# SlaveDual.net
KiCad netlist of a schematic drawn in EAGLE
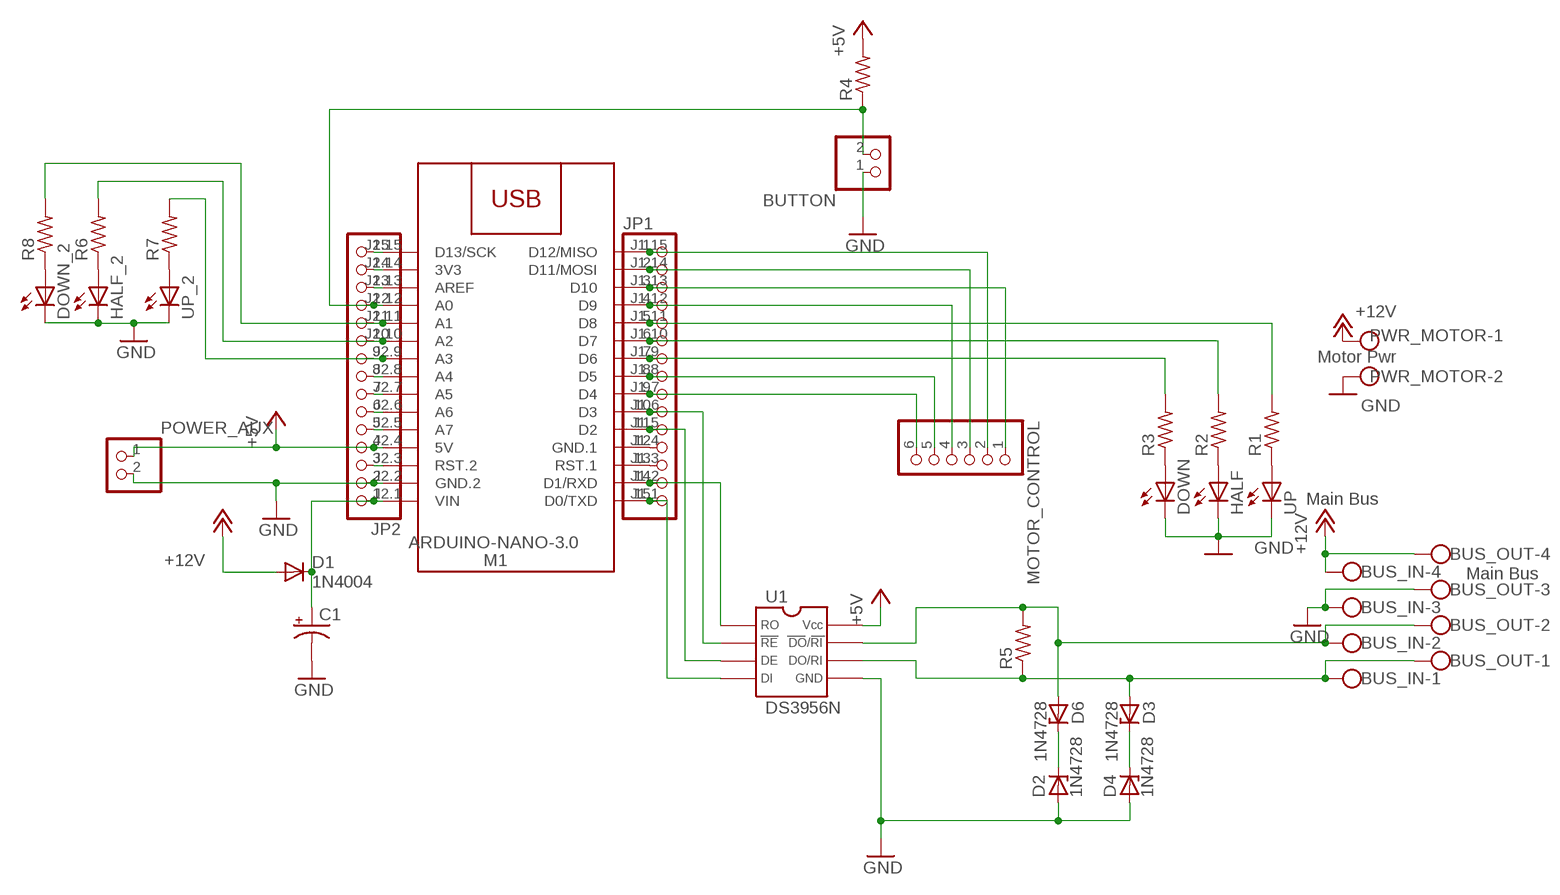
[diagram p0: schematic, sheet 1]

(export (version "E")
  (design (tool "Eeschema 10.0.6"))
  (components
    (comp (ref "BUS_IN")
      (value "Main Bus")
      (footprint "eagle-import:W237-4")
      (libsource (lib "eagle-import") (part "W237-4"))
    )
    (comp (ref "BUS_OUT")
      (value "Main Bus")
      (footprint "eagle-import:W237-4")
      (libsource (lib "eagle-import") (part "W237-4"))
    )
    (comp (ref "BUTTON")
      (value "PINHD-1X2")
      (footprint "eagle-import:1X02")
      (libsource (lib "eagle-import") (part "PINHD-1X2"))
    )
    (comp (ref "C1")
      (value "CPOL-USE3.5-10")
      (footprint "eagle-import:E3,5-10")
      (libsource (lib "eagle-import") (part "CPOL-USE3.5-10"))
    )
    (comp (ref "D1")
      (value "1N4004")
      (footprint "eagle-import:DO41-10")
      (libsource (lib "eagle-import") (part "1N4004"))
    )
    (comp (ref "D2")
      (value "1N4728")
      (footprint "eagle-import:DO41Z10")
      (libsource (lib "eagle-import") (part "1N4728"))
    )
    (comp (ref "D3")
      (value "1N4728")
      (footprint "eagle-import:DO41Z10")
      (libsource (lib "eagle-import") (part "1N4728"))
    )
    (comp (ref "D4")
      (value "1N4728")
      (footprint "eagle-import:DO41Z10")
      (libsource (lib "eagle-import") (part "1N4728"))
    )
    (comp (ref "D6")
      (value "1N4728")
      (footprint "eagle-import:DO41Z10")
      (libsource (lib "eagle-import") (part "1N4728"))
    )
    (comp (ref "DOWN")
      (value "LED5MM")
      (footprint "eagle-import:LED5MM")
      (libsource (lib "eagle-import") (part "LED5MM"))
    )
    (comp (ref "DOWN_2")
      (value "LED5MM")
      (footprint "eagle-import:LED5MM")
      (libsource (lib "eagle-import") (part "LED5MM"))
    )
    (comp (ref "HALF")
      (value "LED5MM")
      (footprint "eagle-import:LED5MM")
      (libsource (lib "eagle-import") (part "LED5MM"))
    )
    (comp (ref "HALF_2")
      (value "LED5MM")
      (footprint "eagle-import:LED5MM")
      (libsource (lib "eagle-import") (part "LED5MM"))
    )
    (comp (ref "JP1")
      (value "PINHD-1X15-CB")
      (footprint "eagle-import:1X15-CB")
      (libsource (lib "eagle-import") (part "PINHD-1X15-CB"))
    )
    (comp (ref "JP2")
      (value "PINHD-1X15-CB")
      (footprint "eagle-import:1X15-CB")
      (libsource (lib "eagle-import") (part "PINHD-1X15-CB"))
    )
    (comp (ref "M1")
      (value "ARDUINO-NANO-3.0")
      (footprint "eagle-import:ARDUINO-NANO-3.0")
      (libsource (lib "eagle-import") (part "ARDUINO-NANO-3.0"))
    )
    (comp (ref "MOTOR_CONTROL")
      (value "PINHD-1X6")
      (footprint "eagle-import:1X06")
      (libsource (lib "eagle-import") (part "PINHD-1X6"))
    )
    (comp (ref "POWER_AUX")
      (value "PINHD-1X2")
      (footprint "eagle-import:1X02")
      (libsource (lib "eagle-import") (part "PINHD-1X2"))
    )
    (comp (ref "PWR_MOTOR")
      (value "Motor Pwr")
      (footprint "eagle-import:W237-102")
      (fields (field (name "MPN") "237-102"))
      (libsource (lib "eagle-import") (part "W237-102"))
    )
    (comp (ref "R1")
      (value "FLIPFLOP-RES")
      (footprint "eagle-import:0805-THM")
      (libsource (lib "eagle-import") (part "FLIPFLOP-RES"))
    )
    (comp (ref "R2")
      (value "FLIPFLOP-RES")
      (footprint "eagle-import:0805-THM")
      (libsource (lib "eagle-import") (part "FLIPFLOP-RES"))
    )
    (comp (ref "R3")
      (value "FLIPFLOP-RES")
      (footprint "eagle-import:0805-THM")
      (libsource (lib "eagle-import") (part "FLIPFLOP-RES"))
    )
    (comp (ref "R4")
      (value "FLIPFLOP-RES")
      (footprint "eagle-import:0805-THM")
      (libsource (lib "eagle-import") (part "FLIPFLOP-RES"))
    )
    (comp (ref "R5")
      (value "FLIPFLOP-RES")
      (footprint "eagle-import:0805-THM")
      (libsource (lib "eagle-import") (part "FLIPFLOP-RES"))
    )
    (comp (ref "R6")
      (value "FLIPFLOP-RES")
      (footprint "eagle-import:0805-THM")
      (libsource (lib "eagle-import") (part "FLIPFLOP-RES"))
    )
    (comp (ref "R7")
      (value "FLIPFLOP-RES")
      (footprint "eagle-import:0805-THM")
      (libsource (lib "eagle-import") (part "FLIPFLOP-RES"))
    )
    (comp (ref "R8")
      (value "FLIPFLOP-RES")
      (footprint "eagle-import:0805-THM")
      (libsource (lib "eagle-import") (part "FLIPFLOP-RES"))
    )
    (comp (ref "U1")
      (value "DS3956N")
      (footprint "eagle-import:DIL08")
      (libsource (lib "eagle-import") (part "DS3956N"))
    )
    (comp (ref "UP")
      (value "LED5MM")
      (footprint "eagle-import:LED5MM")
      (libsource (lib "eagle-import") (part "LED5MM"))
    )
    (comp (ref "UP_2")
      (value "LED5MM")
      (footprint "eagle-import:LED5MM")
      (libsource (lib "eagle-import") (part "LED5MM"))
    )
  )
  (nets
    (net (code "1") (name "+5V") (class "Default")
      (node (ref "JP2") (pin "4") (pinfunction "4_4") (pintype "passive"))
      (node (ref "M1") (pin "J2.4") (pinfunction "5V_J2.4") (pintype "power_in"))
      (node (ref "POWER_AUX") (pin "1") (pinfunction "1_1") (pintype "passive"))
      (node (ref "R4") (pin "2") (pinfunction "2_2") (pintype "passive"))
      (node (ref "U1") (pin "8") (pinfunction "VCC_8") (pintype "bidirectional"))
    )
    (net (code "2") (name "+12V") (class "Default")
      (node (ref "BUS_IN") (pin "4") (pinfunction "KL_4") (pintype "passive"))
      (node (ref "BUS_OUT") (pin "4") (pinfunction "KL_4") (pintype "passive"))
      (node (ref "D1") (pin "A") (pinfunction "A_A") (pintype "passive"))
      (node (ref "PWR_MOTOR") (pin "1") (pinfunction "KL_1") (pintype "passive"))
    )
    (net (code "3") (name "GND") (class "Default")
      (node (ref "BUS_IN") (pin "3") (pinfunction "KL_3") (pintype "passive"))
      (node (ref "BUS_OUT") (pin "3") (pinfunction "KL_3") (pintype "passive"))
      (node (ref "BUTTON") (pin "1") (pinfunction "1_1") (pintype "passive"))
      (node (ref "C1") (pin "-") (pinfunction "-_-") (pintype "passive"))
      (node (ref "D2") (pin "A") (pinfunction "A_A") (pintype "passive"))
      (node (ref "D4") (pin "A") (pinfunction "A_A") (pintype "passive"))
      (node (ref "DOWN") (pin "K") (pinfunction "C_K") (pintype "passive"))
      (node (ref "DOWN_2") (pin "K") (pinfunction "C_K") (pintype "passive"))
      (node (ref "HALF") (pin "K") (pinfunction "C_K") (pintype "passive"))
      (node (ref "HALF_2") (pin "K") (pinfunction "C_K") (pintype "passive"))
      (node (ref "JP2") (pin "2") (pinfunction "2_2") (pintype "passive"))
      (node (ref "M1") (pin "J2.2") (pinfunction "GND.2_J2.2") (pintype "power_in"))
      (node (ref "POWER_AUX") (pin "2") (pinfunction "2_2") (pintype "passive"))
      (node (ref "PWR_MOTOR") (pin "2") (pinfunction "KL_2") (pintype "passive"))
      (node (ref "U1") (pin "5") (pinfunction "GND_5") (pintype "bidirectional"))
      (node (ref "UP") (pin "K") (pinfunction "C_K") (pintype "passive"))
      (node (ref "UP_2") (pin "K") (pinfunction "C_K") (pintype "passive"))
    )
    (net (code "4") (name "Net-(BUS_INA-KL)") (class "Default")
      (node (ref "BUS_IN") (pin "1") (pinfunction "KL_1") (pintype "passive"))
      (node (ref "BUS_OUT") (pin "1") (pinfunction "KL_1") (pintype "passive"))
      (node (ref "D3") (pin "A") (pinfunction "A_A") (pintype "passive"))
      (node (ref "R5") (pin "1") (pinfunction "1_1") (pintype "passive"))
      (node (ref "U1") (pin "6") (pinfunction "DO/RI_6") (pintype "bidirectional"))
    )
    (net (code "5") (name "Net-(BUS_INB-KL)") (class "Default")
      (node (ref "BUS_IN") (pin "2") (pinfunction "KL_2") (pintype "passive"))
      (node (ref "BUS_OUT") (pin "2") (pinfunction "KL_2") (pintype "passive"))
      (node (ref "D6") (pin "A") (pinfunction "A_A") (pintype "passive"))
      (node (ref "R5") (pin "2") (pinfunction "2_2") (pintype "passive"))
      (node (ref "U1") (pin "7") (pinfunction "_DO/RI__7") (pintype "bidirectional"))
    )
    (net (code "6") (name "Net-(D2-PadC)") (class "Default")
      (node (ref "D2") (pin "C") (pinfunction "C_C") (pintype "passive"))
      (node (ref "D6") (pin "C") (pinfunction "C_C") (pintype "passive"))
    )
    (net (code "7") (name "Net-(D3-PadC)") (class "Default")
      (node (ref "D3") (pin "C") (pinfunction "C_C") (pintype "passive"))
      (node (ref "D4") (pin "C") (pinfunction "C_C") (pintype "passive"))
    )
    (net (code "8") (name "Net-(DOWN-PadA)") (class "Default")
      (node (ref "DOWN") (pin "A") (pinfunction "A_A") (pintype "passive"))
      (node (ref "R3") (pin "1") (pinfunction "1_1") (pintype "passive"))
    )
    (net (code "9") (name "Net-(DOWN_2-PadA)") (class "Default")
      (node (ref "DOWN_2") (pin "A") (pinfunction "A_A") (pintype "passive"))
      (node (ref "R8") (pin "1") (pinfunction "1_1") (pintype "passive"))
    )
    (net (code "10") (name "Net-(HALF-PadA)") (class "Default")
      (node (ref "HALF") (pin "A") (pinfunction "A_A") (pintype "passive"))
      (node (ref "R2") (pin "1") (pinfunction "1_1") (pintype "passive"))
    )
    (net (code "11") (name "Net-(HALF_2-PadA)") (class "Default")
      (node (ref "HALF_2") (pin "A") (pinfunction "A_A") (pintype "passive"))
      (node (ref "R6") (pin "1") (pinfunction "1_1") (pintype "passive"))
    )
    (net (code "12") (name "Net-(M1-3V3)") (class "Default")
      (node (ref "JP2") (pin "14") (pinfunction "14_14") (pintype "passive"))
      (node (ref "M1") (pin "J2.14") (pinfunction "3V3_J2.14") (pintype "power_in"))
    )
    (net (code "13") (name "Net-(M1-A0)") (class "Default")
      (node (ref "BUTTON") (pin "2") (pinfunction "2_2") (pintype "passive"))
      (node (ref "JP2") (pin "12") (pinfunction "12_12") (pintype "passive"))
      (node (ref "M1") (pin "J2.12") (pinfunction "A0_J2.12") (pintype "bidirectional"))
      (node (ref "R4") (pin "1") (pinfunction "1_1") (pintype "passive"))
    )
    (net (code "14") (name "Net-(M1-A1)") (class "Default")
      (node (ref "JP2") (pin "11") (pinfunction "11_11") (pintype "passive"))
      (node (ref "M1") (pin "J2.11") (pinfunction "A1_J2.11") (pintype "bidirectional"))
      (node (ref "R8") (pin "2") (pinfunction "2_2") (pintype "passive"))
    )
    (net (code "15") (name "Net-(M1-A2)") (class "Default")
      (node (ref "JP2") (pin "10") (pinfunction "10_10") (pintype "passive"))
      (node (ref "M1") (pin "J2.10") (pinfunction "A2_J2.10") (pintype "bidirectional"))
      (node (ref "R6") (pin "2") (pinfunction "2_2") (pintype "passive"))
    )
    (net (code "16") (name "Net-(M1-A3)") (class "Default")
      (node (ref "JP2") (pin "9") (pinfunction "9_9") (pintype "passive"))
      (node (ref "M1") (pin "J2.9") (pinfunction "A3_J2.9") (pintype "bidirectional"))
      (node (ref "R7") (pin "2") (pinfunction "2_2") (pintype "passive"))
    )
    (net (code "17") (name "Net-(M1-A4)") (class "Default")
      (node (ref "JP2") (pin "8") (pinfunction "8_8") (pintype "passive"))
      (node (ref "M1") (pin "J2.8") (pinfunction "A4_J2.8") (pintype "bidirectional"))
    )
    (net (code "18") (name "Net-(M1-A5)") (class "Default")
      (node (ref "JP2") (pin "7") (pinfunction "7_7") (pintype "passive"))
      (node (ref "M1") (pin "J2.7") (pinfunction "A5_J2.7") (pintype "bidirectional"))
    )
    (net (code "19") (name "Net-(M1-A6)") (class "Default")
      (node (ref "JP2") (pin "6") (pinfunction "6_6") (pintype "passive"))
      (node (ref "M1") (pin "J2.6") (pinfunction "A6_J2.6") (pintype "bidirectional"))
    )
    (net (code "20") (name "Net-(M1-A7)") (class "Default")
      (node (ref "JP2") (pin "5") (pinfunction "5_5") (pintype "passive"))
      (node (ref "M1") (pin "J2.5") (pinfunction "A7_J2.5") (pintype "bidirectional"))
    )
    (net (code "21") (name "Net-(M1-AREF)") (class "Default")
      (node (ref "JP2") (pin "13") (pinfunction "13_13") (pintype "passive"))
      (node (ref "M1") (pin "J2.13") (pinfunction "AREF_J2.13") (pintype "bidirectional"))
    )
    (net (code "22") (name "Net-(M1-D0{slash}TXD)") (class "Default")
      (node (ref "JP1") (pin "15") (pinfunction "15_15") (pintype "passive"))
      (node (ref "M1") (pin "J1.1") (pinfunction "D0/TXD_J1.1") (pintype "bidirectional"))
      (node (ref "U1") (pin "4") (pinfunction "DI_4") (pintype "bidirectional"))
    )
    (net (code "23") (name "Net-(M1-D1{slash}RXD)") (class "Default")
      (node (ref "JP1") (pin "14") (pinfunction "14_14") (pintype "passive"))
      (node (ref "M1") (pin "J1.2") (pinfunction "D1/RXD_J1.2") (pintype "bidirectional"))
      (node (ref "U1") (pin "1") (pinfunction "RO_1") (pintype "bidirectional"))
    )
    (net (code "24") (name "Net-(M1-D2)") (class "Default")
      (node (ref "JP1") (pin "11") (pinfunction "11_11") (pintype "passive"))
      (node (ref "M1") (pin "J1.5") (pinfunction "D2_J1.5") (pintype "bidirectional"))
      (node (ref "U1") (pin "3") (pinfunction "DE_3") (pintype "bidirectional"))
    )
    (net (code "25") (name "Net-(M1-D3)") (class "Default")
      (node (ref "JP1") (pin "10") (pinfunction "10_10") (pintype "passive"))
      (node (ref "M1") (pin "J1.6") (pinfunction "D3_J1.6") (pintype "bidirectional"))
      (node (ref "U1") (pin "2") (pinfunction "_RE__2") (pintype "bidirectional"))
    )
    (net (code "26") (name "Net-(M1-D4)") (class "Default")
      (node (ref "JP1") (pin "9") (pinfunction "9_9") (pintype "passive"))
      (node (ref "M1") (pin "J1.7") (pinfunction "D4_J1.7") (pintype "bidirectional"))
      (node (ref "MOTOR_CONTROL") (pin "6") (pinfunction "6_6") (pintype "passive"))
    )
    (net (code "27") (name "Net-(M1-D5)") (class "Default")
      (node (ref "JP1") (pin "8") (pinfunction "8_8") (pintype "passive"))
      (node (ref "M1") (pin "J1.8") (pinfunction "D5_J1.8") (pintype "bidirectional"))
      (node (ref "MOTOR_CONTROL") (pin "5") (pinfunction "5_5") (pintype "passive"))
    )
    (net (code "28") (name "Net-(M1-D6)") (class "Default")
      (node (ref "JP1") (pin "7") (pinfunction "7_7") (pintype "passive"))
      (node (ref "M1") (pin "J1.9") (pinfunction "D6_J1.9") (pintype "bidirectional"))
      (node (ref "R3") (pin "2") (pinfunction "2_2") (pintype "passive"))
    )
    (net (code "29") (name "Net-(M1-D7)") (class "Default")
      (node (ref "JP1") (pin "6") (pinfunction "6_6") (pintype "passive"))
      (node (ref "M1") (pin "J1.10") (pinfunction "D7_J1.10") (pintype "bidirectional"))
      (node (ref "R2") (pin "2") (pinfunction "2_2") (pintype "passive"))
    )
    (net (code "30") (name "Net-(M1-D8)") (class "Default")
      (node (ref "JP1") (pin "5") (pinfunction "5_5") (pintype "passive"))
      (node (ref "M1") (pin "J1.11") (pinfunction "D8_J1.11") (pintype "bidirectional"))
      (node (ref "R1") (pin "2") (pinfunction "2_2") (pintype "passive"))
    )
    (net (code "31") (name "Net-(M1-D9)") (class "Default")
      (node (ref "JP1") (pin "4") (pinfunction "4_4") (pintype "passive"))
      (node (ref "M1") (pin "J1.12") (pinfunction "D9_J1.12") (pintype "bidirectional"))
      (node (ref "MOTOR_CONTROL") (pin "4") (pinfunction "4_4") (pintype "passive"))
    )
    (net (code "32") (name "Net-(M1-D10)") (class "Default")
      (node (ref "JP1") (pin "3") (pinfunction "3_3") (pintype "passive"))
      (node (ref "M1") (pin "J1.13") (pinfunction "D10_J1.13") (pintype "bidirectional"))
      (node (ref "MOTOR_CONTROL") (pin "1") (pinfunction "1_1") (pintype "passive"))
    )
    (net (code "33") (name "Net-(M1-D11{slash}MOSI)") (class "Default")
      (node (ref "JP1") (pin "2") (pinfunction "2_2") (pintype "passive"))
      (node (ref "M1") (pin "J1.14") (pinfunction "D11/MOSI_J1.14") (pintype "bidirectional"))
      (node (ref "MOTOR_CONTROL") (pin "3") (pinfunction "3_3") (pintype "passive"))
    )
    (net (code "34") (name "Net-(M1-D12{slash}MISO)") (class "Default")
      (node (ref "JP1") (pin "1") (pinfunction "1_1") (pintype "passive"))
      (node (ref "M1") (pin "J1.15") (pinfunction "D12/MISO_J1.15") (pintype "bidirectional"))
      (node (ref "MOTOR_CONTROL") (pin "2") (pinfunction "2_2") (pintype "passive"))
    )
    (net (code "35") (name "Net-(M1-D13{slash}SCK)") (class "Default")
      (node (ref "JP2") (pin "15") (pinfunction "15_15") (pintype "passive"))
      (node (ref "M1") (pin "J2.15") (pinfunction "D13/SCK_J2.15") (pintype "bidirectional"))
    )
    (net (code "36") (name "Net-(M1-GND.1)") (class "Default")
      (node (ref "JP1") (pin "12") (pinfunction "12_12") (pintype "passive"))
      (node (ref "M1") (pin "J1.4") (pinfunction "GND.1_J1.4") (pintype "power_in"))
    )
    (net (code "37") (name "Net-(M1-RST.1)") (class "Default")
      (node (ref "JP1") (pin "13") (pinfunction "13_13") (pintype "passive"))
      (node (ref "M1") (pin "J1.3") (pinfunction "RST.1_J1.3") (pintype "bidirectional"))
    )
    (net (code "38") (name "Net-(M1-RST.2)") (class "Default")
      (node (ref "JP2") (pin "3") (pinfunction "3_3") (pintype "passive"))
      (node (ref "M1") (pin "J2.3") (pinfunction "RST.2_J2.3") (pintype "bidirectional"))
    )
    (net (code "39") (name "Net-(M1-VIN)") (class "Default")
      (node (ref "C1") (pin "+") (pinfunction "+_+") (pintype "passive"))
      (node (ref "D1") (pin "C") (pinfunction "C_C") (pintype "passive"))
      (node (ref "JP2") (pin "1") (pinfunction "1_1") (pintype "passive"))
      (node (ref "M1") (pin "J2.1") (pinfunction "VIN_J2.1") (pintype "power_in"))
    )
    (net (code "40") (name "Net-(R1-Pad1)") (class "Default")
      (node (ref "R1") (pin "1") (pinfunction "1_1") (pintype "passive"))
      (node (ref "UP") (pin "A") (pinfunction "A_A") (pintype "passive"))
    )
    (net (code "41") (name "Net-(R7-Pad1)") (class "Default")
      (node (ref "R7") (pin "1") (pinfunction "1_1") (pintype "passive"))
      (node (ref "UP_2") (pin "A") (pinfunction "A_A") (pintype "passive"))
    )
  )
)
